# Arduino.net
KiCad netlist of a schematic drawn in Altium Designer
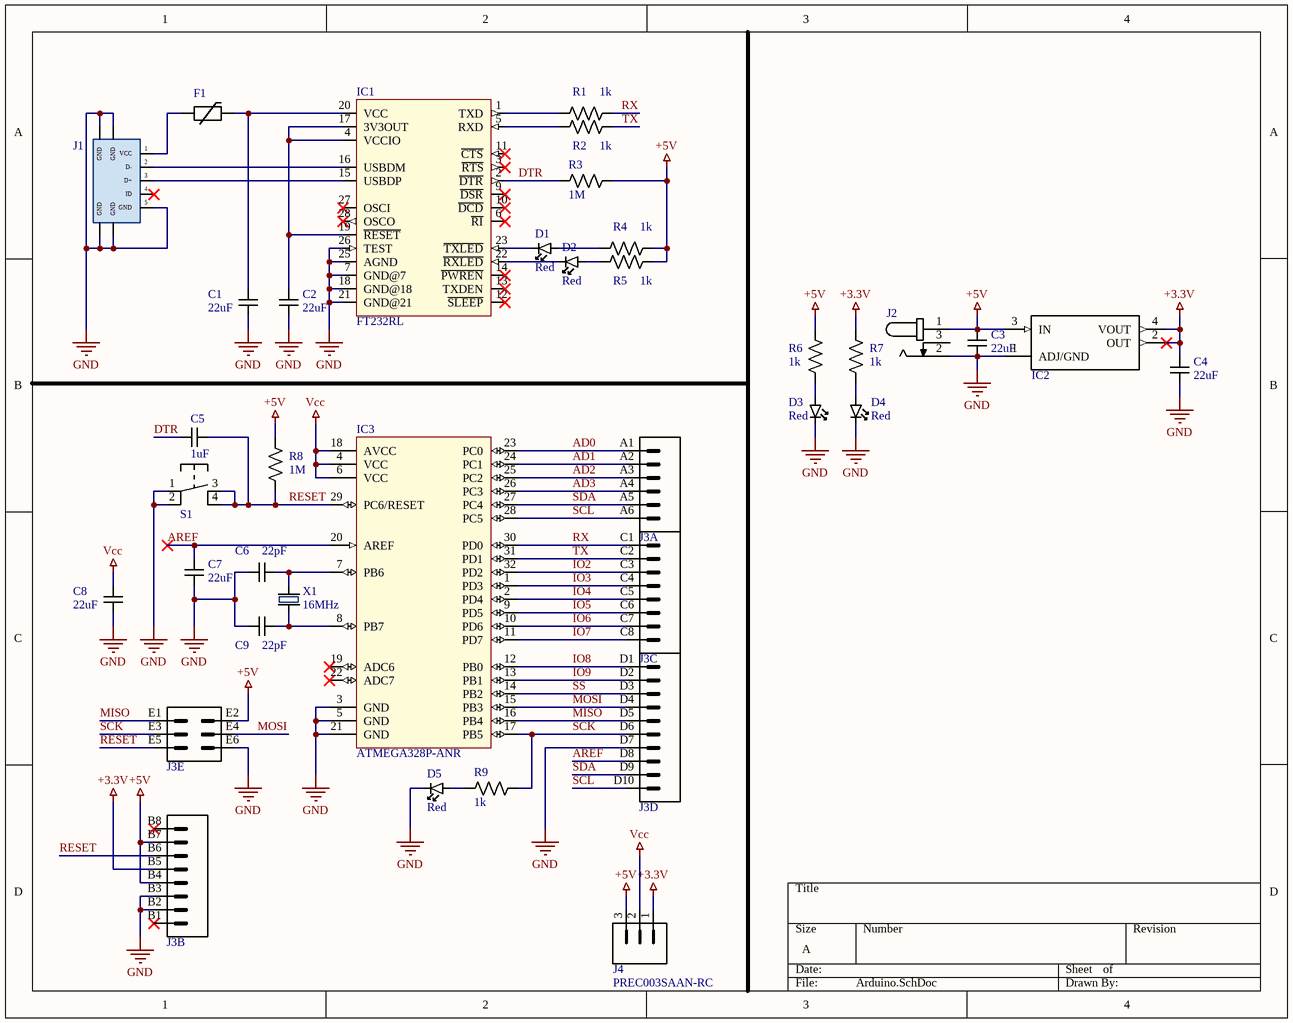
[diagram p0: Arduino.SchDoc]

(export (version "E")
  (design (tool "Eeschema 10.0.6"))
  (components
    (comp (ref "C1")
      (value "22uF")
      (footprint "CAP1206")
      (description "22µF ±20% 16V Ceramic Capacitor X5R 1206 (3216 Metric)")
      (fields (field (name "DIGIKEY PART") "1276-2728-1-ND"))
      (libsource (lib "Arduino") (part "1206_22uF"))
    )
    (comp (ref "C2")
      (value "22uF")
      (footprint "CAP1206")
      (description "22µF ±20% 16V Ceramic Capacitor X5R 1206 (3216 Metric)")
      (fields (field (name "DIGIKEY PART") "1276-2728-1-ND"))
      (libsource (lib "Arduino") (part "1206_22uF"))
    )
    (comp (ref "C3")
      (value "22uF")
      (footprint "CAP1206")
      (description "22µF ±20% 16V Ceramic Capacitor X5R 1206 (3216 Metric)")
      (fields (field (name "DIGIKEY PART") "1276-2728-1-ND"))
      (libsource (lib "Arduino") (part "1206_22uF"))
    )
    (comp (ref "C4")
      (value "22uF")
      (footprint "CAP1206")
      (description "22µF ±20% 16V Ceramic Capacitor X5R 1206 (3216 Metric)")
      (fields (field (name "DIGIKEY PART") "1276-2728-1-ND"))
      (libsource (lib "Arduino") (part "1206_22uF"))
    )
    (comp (ref "C5")
      (value "1uF")
      (footprint "CAP1206")
      (description "1µF ±20% 16V Ceramic Capacitor X7R 1206 (3216 Metric)")
      (fields (field (name "DIGIKEY PART") "399-8150-1-ND"))
      (libsource (lib "Arduino") (part "1206_1uF"))
    )
    (comp (ref "C6")
      (value "22pF")
      (footprint "CAP1206")
      (description "22pF ±5% 16V Ceramic Capacitor C0G, NP0 1206 (3216 Metric)")
      (fields (field (name "DIGIKEY PART") "732-7867-1-ND"))
      (libsource (lib "Arduino") (part "1206_22pF"))
    )
    (comp (ref "C7")
      (value "22uF")
      (footprint "CAP1206")
      (description "22µF ±20% 16V Ceramic Capacitor X5R 1206 (3216 Metric)")
      (fields (field (name "DIGIKEY PART") "1276-2728-1-ND"))
      (libsource (lib "Arduino") (part "1206_22uF"))
    )
    (comp (ref "C8")
      (value "22uF")
      (footprint "CAP1206")
      (description "22µF ±20% 16V Ceramic Capacitor X5R 1206 (3216 Metric)")
      (fields (field (name "DIGIKEY PART") "1276-2728-1-ND"))
      (libsource (lib "Arduino") (part "1206_22uF"))
    )
    (comp (ref "C9")
      (value "22pF")
      (footprint "CAP1206")
      (description "22pF ±5% 16V Ceramic Capacitor C0G, NP0 1206 (3216 Metric)")
      (fields (field (name "DIGIKEY PART") "732-7867-1-ND"))
      (libsource (lib "Arduino") (part "1206_22pF"))
    )
    (comp (ref "D1")
      (value "Red")
      (footprint "LED")
      (description "Red 638nm LED Indication - Discrete 1.8V 1206 (3216 Metric)")
      (fields (field (name "DIGIKEY PART") "160-1167-1-ND"))
      (libsource (lib "Arduino") (part "1206_RED_LED"))
    )
    (comp (ref "D2")
      (value "Red")
      (footprint "LED")
      (description "Red 638nm LED Indication - Discrete 1.8V 1206 (3216 Metric)")
      (fields (field (name "DIGIKEY PART") "160-1167-1-ND"))
      (libsource (lib "Arduino") (part "1206_RED_LED"))
    )
    (comp (ref "D3")
      (value "Red")
      (footprint "LED")
      (description "Red 638nm LED Indication - Discrete 1.8V 1206 (3216 Metric)")
      (fields (field (name "DIGIKEY PART") "160-1167-1-ND"))
      (libsource (lib "Arduino") (part "1206_RED_LED"))
    )
    (comp (ref "D4")
      (value "Red")
      (footprint "LED")
      (description "Red 638nm LED Indication - Discrete 1.8V 1206 (3216 Metric)")
      (fields (field (name "DIGIKEY PART") "160-1167-1-ND"))
      (libsource (lib "Arduino") (part "1206_RED_LED"))
    )
    (comp (ref "D5")
      (value "Red")
      (footprint "LED")
      (description "Red 638nm LED Indication - Discrete 1.8V 1206 (3216 Metric)")
      (fields (field (name "DIGIKEY PART") "160-1167-1-ND"))
      (libsource (lib "Arduino") (part "1206_RED_LED"))
    )
    (comp (ref "F1")
      (value "MF-MSMF050-2")
      (footprint "FUSE")
      (description "Polymeric PTC Resettable Fuse 15V 500mA Ih Surface Mount 1812 (4532 Metric), Concave")
      (fields (field (name "DIGIKEY PART") "MF-MSMF050-2CT-ND"))
      (libsource (lib "Arduino") (part "Fuse"))
    )
    (comp (ref "IC1")
      (value "FT232RL")
      (footprint "SSOP-28")
      (description "USB Bridge, USB to UART USB 2.0 UART Interface 28-SSOP")
      (fields (field (name "DIGIKEY PART") "768-1007-1-ND"))
      (libsource (lib "Arduino") (part "FTDI"))
    )
    (comp (ref "IC2")
      (value "AZ1117CH-3.3TRG1")
      (footprint "SOT223")
      (description "Linear Voltage Regulator IC Positive Fixed 1 Output 1A SOT-223")
      (fields (field (name "DIGIKEY PART") "AZ1117CH-3.3TRG1DICT-ND"))
      (libsource (lib "Arduino") (part "3.3V_LDO"))
    )
    (comp (ref "IC3")
      (value "ATMEGA328P-ANR")
      (footprint "TQFP")
      (description "AVR AVR® ATmega Microcontroller IC 8-Bit 20MHz 32KB (16K x 16) FLASH 32-TQFP (7x7)")
      (fields (field (name "DIGIKEY PART") "ATMEGA328P-ANRCT-ND"))
      (libsource (lib "Arduino") (part "ATMega328P"))
    )
    (comp (ref "J1")
      (value "XM7D-0512")
      (footprint "XM7D-0512")
      (description "USB - mini B USB 2.0 Receptacle Connector 5 Position Through Hole, Right Angle")
      (fields (field (name "DIGIKEY PART") "OR1205-ND"))
      (libsource (lib "Arduino") (part "USB"))
    )
    (comp (ref "J2")
      (value "Power Jack")
      (footprint "Power_Jack")
      (description "Power Barrel Connector Jack 2.10mm ID (0.083\"), 5.50mm OD (0.217\") Through Hole, Right Angle")
      (fields (field (name "DIGIKEY PART") "CP-102A-ND"))
      (libsource (lib "Arduino") (part "Power Jack"))
    )
    (comp (ref "J3")
      (value "Arduino_Shield")
      (footprint "ARDUINO_SHIELD")
      (libsource (lib "") (part "Arduino_Shield_1"))
    )
    (comp (ref "J4")
      (value "PREC003SAAN-RC")
      (footprint "3_PIN")
      (description "Connector Header Through Hole 3 position 0.100\" (2.54mm)")
      (fields (field (name "DIGIKEY PART") "S1012EC-03-ND"))
      (libsource (lib "Arduino") (part "3_PIN"))
    )
    (comp (ref "R1")
      (value "1k")
      (footprint "RES1206")
      (description "1 kOhms ±1% 0.5W, 1/2W Chip Resistor 1206 (3216 Metric) Anti-Sulfur, Moisture Resistant Thin Film")
      (fields (field (name "DIGIKEY PART") "RNCP1206FTD1K00CT-ND"))
      (libsource (lib "Arduino") (part "1206_1K"))
    )
    (comp (ref "R2")
      (value "1k")
      (footprint "RES1206")
      (description "1 kOhms ±1% 0.5W, 1/2W Chip Resistor 1206 (3216 Metric) Anti-Sulfur, Moisture Resistant Thin Film")
      (fields (field (name "DIGIKEY PART") "RNCP1206FTD1K00CT-ND"))
      (libsource (lib "Arduino") (part "1206_1K"))
    )
    (comp (ref "R3")
      (value "1M")
      (footprint "RES1206")
      (description "1 MOhms ±5% 0.25W, 1/4W Chip Resistor 1206 (3216 Metric) Automotive AEC-Q200 Thick Film")
      (fields (field (name "DIGIKEY PART") "Number RMCF1206JT1M00CT-ND"))
      (libsource (lib "Arduino") (part "1206_1M"))
    )
    (comp (ref "R4")
      (value "1k")
      (footprint "RES1206")
      (description "1 kOhms ±1% 0.5W, 1/2W Chip Resistor 1206 (3216 Metric) Anti-Sulfur, Moisture Resistant Thin Film")
      (fields (field (name "DIGIKEY PART") "RNCP1206FTD1K00CT-ND"))
      (libsource (lib "Arduino") (part "1206_1K"))
    )
    (comp (ref "R5")
      (value "1k")
      (footprint "RES1206")
      (description "1 kOhms ±1% 0.5W, 1/2W Chip Resistor 1206 (3216 Metric) Anti-Sulfur, Moisture Resistant Thin Film")
      (fields (field (name "DIGIKEY PART") "RNCP1206FTD1K00CT-ND"))
      (libsource (lib "Arduino") (part "1206_1K"))
    )
    (comp (ref "R6")
      (value "1k")
      (footprint "RES1206")
      (description "1 kOhms ±1% 0.5W, 1/2W Chip Resistor 1206 (3216 Metric) Anti-Sulfur, Moisture Resistant Thin Film")
      (fields (field (name "DIGIKEY PART") "RNCP1206FTD1K00CT-ND"))
      (libsource (lib "Arduino") (part "1206_1K"))
    )
    (comp (ref "R7")
      (value "1k")
      (footprint "RES1206")
      (description "1 kOhms ±1% 0.5W, 1/2W Chip Resistor 1206 (3216 Metric) Anti-Sulfur, Moisture Resistant Thin Film")
      (fields (field (name "DIGIKEY PART") "RNCP1206FTD1K00CT-ND"))
      (libsource (lib "Arduino") (part "1206_1K"))
    )
    (comp (ref "R8")
      (value "1M")
      (footprint "RES1206")
      (description "1 MOhms ±5% 0.25W, 1/4W Chip Resistor 1206 (3216 Metric) Automotive AEC-Q200 Thick Film")
      (fields (field (name "DIGIKEY PART") "Number RMCF1206JT1M00CT-ND"))
      (libsource (lib "Arduino") (part "1206_1M"))
    )
    (comp (ref "R9")
      (value "1k")
      (footprint "RES1206")
      (description "1 kOhms ±1% 0.5W, 1/2W Chip Resistor 1206 (3216 Metric) Anti-Sulfur, Moisture Resistant Thin Film")
      (fields (field (name "DIGIKEY PART") "RNCP1206FTD1K00CT-ND"))
      (libsource (lib "Arduino") (part "1206_1K"))
    )
    (comp (ref "S1")
      (value "TL3305AF160QG")
      (footprint "Switch")
      (description "Tactile Switch SPST-NO Top Actuated Surface Mount")
      (fields (field (name "DIGIKEY PART") "EG5350CT-ND"))
      (libsource (lib "Arduino") (part "Push_Button"))
    )
    (comp (ref "X1")
      (value "16MHz")
      (footprint "Crystal")
      (description "16MHz ±30ppm Crystal 18pF 40 Ohms HC-49/US")
      (fields (field (name "DIGIKEY PART") "535-10226-1-ND"))
      (libsource (lib "Arduino") (part "16MHz_Crystal"))
    )
  )
  (nets
    (net (code "1") (name "+3.3V") (class "Default")
      (node (ref "C4") (pin "2") (pinfunction "2_2") (pintype "passive"))
      (node (ref "IC2") (pin "2") (pinfunction "OUT_2") (pintype "output"))
      (node (ref "IC2") (pin "4") (pinfunction "VOUT_4") (pintype "output"))
      (node (ref "J3") (pin "B5") (pinfunction "5_B5") (pintype "passive"))
      (node (ref "J4") (pin "1") (pinfunction "1_1") (pintype "passive"))
      (node (ref "R7") (pin "2") (pintype "passive"))
    )
    (net (code "2") (name "+5V") (class "Default")
      (node (ref "C3") (pin "1") (pinfunction "1_1") (pintype "passive"))
      (node (ref "IC2") (pin "3") (pinfunction "IN_3") (pintype "input"))
      (node (ref "J2") (pin "1") (pinfunction "1_1") (pintype "passive"))
      (node (ref "J3") (pin "B4") (pinfunction "4_B4") (pintype "passive"))
      (node (ref "J3") (pin "B7") (pinfunction "7_B7") (pintype "passive"))
      (node (ref "J3") (pin "E2") (pinfunction "4_E2") (pintype "passive"))
      (node (ref "J4") (pin "3") (pinfunction "3_3") (pintype "passive"))
      (node (ref "R3") (pin "1") (pintype "passive"))
      (node (ref "R4") (pin "2") (pintype "passive"))
      (node (ref "R5") (pin "2") (pintype "passive"))
      (node (ref "R6") (pin "2") (pintype "passive"))
      (node (ref "R8") (pin "2") (pintype "passive"))
    )
    (net (code "3") (name "/AD0") (class "Default")
      (node (ref "IC3") (pin "23") (pinfunction "PC0_23") (pintype "bidirectional"))
      (node (ref "J3") (pin "A1") (pinfunction "1_A1") (pintype "passive"))
    )
    (net (code "4") (name "/AD1") (class "Default")
      (node (ref "IC3") (pin "24") (pinfunction "PC1_24") (pintype "bidirectional"))
      (node (ref "J3") (pin "A2") (pinfunction "2_A2") (pintype "passive"))
    )
    (net (code "5") (name "/AD2") (class "Default")
      (node (ref "IC3") (pin "25") (pinfunction "PC2_25") (pintype "bidirectional"))
      (node (ref "J3") (pin "A3") (pinfunction "3_A3") (pintype "passive"))
    )
    (net (code "6") (name "/AD3") (class "Default")
      (node (ref "IC3") (pin "26") (pinfunction "PC3_26") (pintype "bidirectional"))
      (node (ref "J3") (pin "A4") (pinfunction "4_A4") (pintype "passive"))
    )
    (net (code "7") (name "/AREF") (class "Default")
      (node (ref "C7") (pin "2") (pinfunction "2_2") (pintype "passive"))
      (node (ref "IC3") (pin "20") (pinfunction "AREF_20") (pintype "input"))
      (node (ref "J3") (pin "D8") (pinfunction "8_D8") (pintype "passive"))
    )
    (net (code "8") (name "/DTR") (class "Default")
      (node (ref "C5") (pin "1") (pinfunction "1_1") (pintype "passive"))
      (node (ref "IC1") (pin "2") (pinfunction "~{DTR}_2") (pintype "output"))
      (node (ref "R3") (pin "2") (pintype "passive"))
    )
    (net (code "9") (name "/IO2") (class "Default")
      (node (ref "IC3") (pin "32") (pinfunction "PD2_32") (pintype "bidirectional"))
      (node (ref "J3") (pin "C3") (pinfunction "3_C3") (pintype "passive"))
    )
    (net (code "10") (name "/IO3") (class "Default")
      (node (ref "IC3") (pin "1") (pinfunction "PD3_1") (pintype "bidirectional"))
      (node (ref "J3") (pin "C4") (pinfunction "4_C4") (pintype "passive"))
    )
    (net (code "11") (name "/IO4") (class "Default")
      (node (ref "IC3") (pin "2") (pinfunction "PD4_2") (pintype "bidirectional"))
      (node (ref "J3") (pin "C5") (pinfunction "5_C5") (pintype "passive"))
    )
    (net (code "12") (name "/IO5") (class "Default")
      (node (ref "IC3") (pin "9") (pinfunction "PD5_9") (pintype "bidirectional"))
      (node (ref "J3") (pin "C6") (pinfunction "6_C6") (pintype "passive"))
    )
    (net (code "13") (name "/IO6") (class "Default")
      (node (ref "IC3") (pin "10") (pinfunction "PD6_10") (pintype "bidirectional"))
      (node (ref "J3") (pin "C7") (pinfunction "7_C7") (pintype "passive"))
    )
    (net (code "14") (name "/IO7") (class "Default")
      (node (ref "IC3") (pin "11") (pinfunction "PD7_11") (pintype "bidirectional"))
      (node (ref "J3") (pin "C8") (pinfunction "8_C8") (pintype "passive"))
    )
    (net (code "15") (name "/IO8") (class "Default")
      (node (ref "IC3") (pin "12") (pinfunction "PB0_12") (pintype "bidirectional"))
      (node (ref "J3") (pin "D1") (pinfunction "1_D1") (pintype "passive"))
    )
    (net (code "16") (name "/IO9") (class "Default")
      (node (ref "IC3") (pin "13") (pinfunction "PB1_13") (pintype "bidirectional"))
      (node (ref "J3") (pin "D2") (pinfunction "2_D2") (pintype "passive"))
    )
    (net (code "17") (name "/MISO") (class "Default")
      (node (ref "IC3") (pin "16") (pinfunction "PB4_16") (pintype "bidirectional"))
      (node (ref "J3") (pin "D5") (pinfunction "5_D5") (pintype "passive"))
      (node (ref "J3") (pin "E1") (pinfunction "1_E1") (pintype "passive"))
    )
    (net (code "18") (name "/MOSI") (class "Default")
      (node (ref "IC3") (pin "15") (pinfunction "PB3_15") (pintype "bidirectional"))
      (node (ref "J3") (pin "D4") (pinfunction "4_D4") (pintype "passive"))
      (node (ref "J3") (pin "E4") (pinfunction "5_E4") (pintype "passive"))
    )
    (net (code "19") (name "/RESET") (class "Default")
      (node (ref "C5") (pin "2") (pinfunction "2_2") (pintype "passive"))
      (node (ref "IC3") (pin "29") (pinfunction "PC6/RESET_29") (pintype "bidirectional"))
      (node (ref "J3") (pin "B6") (pinfunction "6_B6") (pintype "passive"))
      (node (ref "J3") (pin "E5") (pinfunction "3_E5") (pintype "passive"))
      (node (ref "R8") (pin "1") (pintype "passive"))
      (node (ref "S1") (pin "3") (pinfunction "3_3") (pintype "passive"))
      (node (ref "S1") (pin "4") (pinfunction "4_4") (pintype "passive"))
    )
    (net (code "20") (name "/RX") (class "Default")
      (node (ref "IC3") (pin "30") (pinfunction "PD0_30") (pintype "bidirectional"))
      (node (ref "J3") (pin "C1") (pinfunction "1_C1") (pintype "passive"))
      (node (ref "R1") (pin "2") (pintype "passive"))
    )
    (net (code "21") (name "/SCK") (class "Default")
      (node (ref "IC3") (pin "17") (pinfunction "PB5_17") (pintype "bidirectional"))
      (node (ref "J3") (pin "D6") (pinfunction "6_D6") (pintype "passive"))
      (node (ref "J3") (pin "E3") (pinfunction "2_E3") (pintype "passive"))
      (node (ref "R9") (pin "2") (pintype "passive"))
    )
    (net (code "22") (name "/SCL") (class "Default")
      (node (ref "IC3") (pin "28") (pinfunction "PC5_28") (pintype "bidirectional"))
      (node (ref "J3") (pin "A6") (pinfunction "6_A6") (pintype "passive"))
      (node (ref "J3") (pin "D10") (pinfunction "10_D10") (pintype "passive"))
    )
    (net (code "23") (name "/SDA") (class "Default")
      (node (ref "IC3") (pin "27") (pinfunction "PC4_27") (pintype "bidirectional"))
      (node (ref "J3") (pin "A5") (pinfunction "5_A5") (pintype "passive"))
      (node (ref "J3") (pin "D9") (pinfunction "9_D9") (pintype "passive"))
    )
    (net (code "24") (name "/SS") (class "Default")
      (node (ref "IC3") (pin "14") (pinfunction "PB2_14") (pintype "bidirectional"))
      (node (ref "J3") (pin "D3") (pinfunction "3_D3") (pintype "passive"))
    )
    (net (code "25") (name "/TX") (class "Default")
      (node (ref "IC3") (pin "31") (pinfunction "PD1_31") (pintype "bidirectional"))
      (node (ref "J3") (pin "C2") (pinfunction "2_C2") (pintype "passive"))
      (node (ref "R2") (pin "2") (pintype "passive"))
    )
    (net (code "26") (name "GND") (class "Default")
      (node (ref "C1") (pin "1") (pinfunction "1_1") (pintype "passive"))
      (node (ref "C2") (pin "1") (pinfunction "1_1") (pintype "passive"))
      (node (ref "C3") (pin "2") (pinfunction "2_2") (pintype "passive"))
      (node (ref "C4") (pin "1") (pinfunction "1_1") (pintype "passive"))
      (node (ref "C6") (pin "1") (pinfunction "1_1") (pintype "passive"))
      (node (ref "C7") (pin "1") (pinfunction "1_1") (pintype "passive"))
      (node (ref "C8") (pin "1") (pinfunction "1_1") (pintype "passive"))
      (node (ref "C9") (pin "1") (pinfunction "1_1") (pintype "passive"))
      (node (ref "D3") (pin "1") (pinfunction "1_1") (pintype "passive"))
      (node (ref "D4") (pin "1") (pinfunction "1_1") (pintype "passive"))
      (node (ref "D5") (pin "1") (pinfunction "1_1") (pintype "passive"))
      (node (ref "IC1") (pin "18") (pinfunction "GND@18_18") (pintype "power_in"))
      (node (ref "IC1") (pin "21") (pinfunction "GND@21_21") (pintype "power_in"))
      (node (ref "IC1") (pin "25") (pinfunction "AGND_25") (pintype "power_in"))
      (node (ref "IC1") (pin "26") (pinfunction "TEST_26") (pintype "input"))
      (node (ref "IC1") (pin "7") (pinfunction "GND@7_7") (pintype "power_in"))
      (node (ref "IC2") (pin "1") (pinfunction "ADJ/GND_1") (pintype "passive"))
      (node (ref "IC3") (pin "21") (pinfunction "GND_21") (pintype "power_in"))
      (node (ref "IC3") (pin "3") (pinfunction "GND_3") (pintype "power_in"))
      (node (ref "IC3") (pin "5") (pinfunction "GND_5") (pintype "power_in"))
      (node (ref "J1") (pin "5") (pinfunction "GND_5") (pintype "passive"))
      (node (ref "J1") (pin "SH1") (pinfunction "GND_SH1") (pintype "passive"))
      (node (ref "J1") (pin "SH2") (pinfunction "GND_SH2") (pintype "passive"))
      (node (ref "J1") (pin "SH3") (pinfunction "GND_SH3") (pintype "passive"))
      (node (ref "J1") (pin "SH4") (pinfunction "GND_SH4") (pintype "passive"))
      (node (ref "J2") (pin "2") (pinfunction "2_2") (pintype "passive"))
      (node (ref "J3") (pin "B2") (pinfunction "2_B2") (pintype "passive"))
      (node (ref "J3") (pin "B3") (pinfunction "3_B3") (pintype "passive"))
      (node (ref "J3") (pin "D7") (pinfunction "7_D7") (pintype "passive"))
      (node (ref "J3") (pin "E6") (pinfunction "6_E6") (pintype "passive"))
      (node (ref "S1") (pin "1") (pinfunction "1_1") (pintype "passive"))
      (node (ref "S1") (pin "2") (pinfunction "2_2") (pintype "passive"))
    )
    (net (code "27") (name "Net-(D1-Pad2)") (class "Default")
      (node (ref "D1") (pin "2") (pinfunction "2_2") (pintype "passive"))
      (node (ref "R4") (pin "1") (pintype "passive"))
    )
    (net (code "28") (name "Net-(D2-Pad2)") (class "Default")
      (node (ref "D2") (pin "2") (pinfunction "2_2") (pintype "passive"))
      (node (ref "R5") (pin "1") (pintype "passive"))
    )
    (net (code "29") (name "Net-(D3-Pad2)") (class "Default")
      (node (ref "D3") (pin "2") (pinfunction "2_2") (pintype "passive"))
      (node (ref "R6") (pin "1") (pintype "passive"))
    )
    (net (code "30") (name "Net-(D4-Pad2)") (class "Default")
      (node (ref "D4") (pin "2") (pinfunction "2_2") (pintype "passive"))
      (node (ref "R7") (pin "1") (pintype "passive"))
    )
    (net (code "31") (name "Net-(D5-Pad2)") (class "Default")
      (node (ref "D5") (pin "2") (pinfunction "2_2") (pintype "passive"))
      (node (ref "R9") (pin "1") (pintype "passive"))
    )
    (net (code "32") (name "Net-(IC1-3V3OUT)") (class "Default")
      (node (ref "C2") (pin "2") (pinfunction "2_2") (pintype "passive"))
      (node (ref "IC1") (pin "17") (pinfunction "3V3OUT_17") (pintype "power_in"))
      (node (ref "IC1") (pin "19") (pinfunction "~{RESET}_19") (pintype "passive"))
      (node (ref "IC1") (pin "4") (pinfunction "VCCIO_4") (pintype "power_in"))
    )
    (net (code "33") (name "Net-(IC1-RXD)") (class "Default")
      (node (ref "IC1") (pin "5") (pinfunction "RXD_5") (pintype "input"))
      (node (ref "R2") (pin "1") (pintype "passive"))
    )
    (net (code "34") (name "Net-(IC1-TXD)") (class "Default")
      (node (ref "IC1") (pin "1") (pinfunction "TXD_1") (pintype "output"))
      (node (ref "R1") (pin "1") (pintype "passive"))
    )
    (net (code "35") (name "Net-(IC1-USBDM)") (class "Default")
      (node (ref "IC1") (pin "16") (pinfunction "USBDM_16") (pintype "bidirectional"))
      (node (ref "J1") (pin "2") (pinfunction "D-_2") (pintype "passive"))
    )
    (net (code "36") (name "Net-(IC1-USBDP)") (class "Default")
      (node (ref "IC1") (pin "15") (pinfunction "USBDP_15") (pintype "bidirectional"))
      (node (ref "J1") (pin "3") (pinfunction "D+_3") (pintype "passive"))
    )
    (net (code "37") (name "Net-(IC1-VCC)") (class "Default")
      (node (ref "C1") (pin "2") (pinfunction "2_2") (pintype "passive"))
      (node (ref "F1") (pin "2") (pinfunction "2_2") (pintype "passive"))
      (node (ref "IC1") (pin "20") (pinfunction "VCC_20") (pintype "power_in"))
    )
    (net (code "38") (name "Net-(IC1-~{RXLED})") (class "Default")
      (node (ref "D2") (pin "1") (pinfunction "1_1") (pintype "passive"))
      (node (ref "IC1") (pin "22") (pinfunction "~{RXLED}_22") (pintype "input"))
    )
    (net (code "39") (name "Net-(IC1-~{TXLED})") (class "Default")
      (node (ref "D1") (pin "1") (pinfunction "1_1") (pintype "passive"))
      (node (ref "IC1") (pin "23") (pinfunction "~{TXLED}_23") (pintype "input"))
    )
    (net (code "40") (name "Net-(IC3-PB6)") (class "Default")
      (node (ref "C6") (pin "2") (pinfunction "2_2") (pintype "passive"))
      (node (ref "IC3") (pin "7") (pinfunction "PB6_7") (pintype "bidirectional"))
      (node (ref "X1") (pin "2") (pinfunction "2_2") (pintype "passive"))
    )
    (net (code "41") (name "Net-(IC3-PB7)") (class "Default")
      (node (ref "C9") (pin "2") (pinfunction "2_2") (pintype "passive"))
      (node (ref "IC3") (pin "8") (pinfunction "PB7_8") (pintype "bidirectional"))
      (node (ref "X1") (pin "1") (pinfunction "1_1") (pintype "passive"))
    )
    (net (code "42") (name "Net-(J1-VCC)") (class "Default")
      (node (ref "F1") (pin "1") (pinfunction "1_1") (pintype "passive"))
      (node (ref "J1") (pin "1") (pinfunction "VCC_1") (pintype "passive"))
    )
    (net (code "43") (name "Vcc") (class "Default")
      (node (ref "C8") (pin "2") (pinfunction "2_2") (pintype "passive"))
      (node (ref "IC3") (pin "18") (pinfunction "AVCC_18") (pintype "power_in"))
      (node (ref "IC3") (pin "4") (pinfunction "VCC_4") (pintype "power_in"))
      (node (ref "IC3") (pin "6") (pinfunction "VCC_6") (pintype "power_in"))
      (node (ref "J4") (pin "2") (pinfunction "2_2") (pintype "passive"))
    )
    (net (code "44") (name "unconnected-(IC1-OSCI-Pad27)") (class "Default")
      (node (ref "IC1") (pin "27") (pinfunction "OSCI_27") (pintype "passive+no_connect"))
    )
    (net (code "45") (name "unconnected-(IC1-OSCO-Pad28)") (class "Default")
      (node (ref "IC1") (pin "28") (pinfunction "OSCO_28") (pintype "output+no_connect"))
    )
    (net (code "46") (name "unconnected-(IC1-TXDEN-Pad13)") (class "Default")
      (node (ref "IC1") (pin "13") (pinfunction "TXDEN_13") (pintype "passive+no_connect"))
    )
    (net (code "47") (name "unconnected-(IC1-~{CTS}-Pad11)") (class "Default")
      (node (ref "IC1") (pin "11") (pinfunction "~{CTS}_11") (pintype "input+no_connect"))
    )
    (net (code "48") (name "unconnected-(IC1-~{DCD}-Pad10)") (class "Default")
      (node (ref "IC1") (pin "10") (pinfunction "~{DCD}_10") (pintype "passive+no_connect"))
    )
    (net (code "49") (name "unconnected-(IC1-~{DSR}-Pad9)") (class "Default")
      (node (ref "IC1") (pin "9") (pinfunction "~{DSR}_9") (pintype "passive+no_connect"))
    )
    (net (code "50") (name "unconnected-(IC1-~{PWREN}-Pad14)") (class "Default")
      (node (ref "IC1") (pin "14") (pinfunction "~{PWREN}_14") (pintype "passive+no_connect"))
    )
    (net (code "51") (name "unconnected-(IC1-~{RI}-Pad6)") (class "Default")
      (node (ref "IC1") (pin "6") (pinfunction "~{RI}_6") (pintype "passive+no_connect"))
    )
    (net (code "52") (name "unconnected-(IC1-~{RTS}-Pad3)") (class "Default")
      (node (ref "IC1") (pin "3") (pinfunction "~{RTS}_3") (pintype "output+no_connect"))
    )
    (net (code "53") (name "unconnected-(IC1-~{SLEEP}-Pad12)") (class "Default")
      (node (ref "IC1") (pin "12") (pinfunction "~{SLEEP}_12") (pintype "passive+no_connect"))
    )
    (net (code "54") (name "unconnected-(IC3-ADC6-Pad19)") (class "Default")
      (node (ref "IC3") (pin "19") (pinfunction "ADC6_19") (pintype "bidirectional+no_connect"))
    )
    (net (code "55") (name "unconnected-(IC3-ADC7-Pad22)") (class "Default")
      (node (ref "IC3") (pin "22") (pinfunction "ADC7_22") (pintype "bidirectional+no_connect"))
    )
    (net (code "56") (name "unconnected-(J1-ID-Pad4)") (class "Default")
      (node (ref "J1") (pin "4") (pinfunction "ID_4") (pintype "passive+no_connect"))
    )
    (net (code "57") (name "unconnected-(J2-Pad3)") (class "Default")
      (node (ref "J2") (pin "3") (pinfunction "3_3") (pintype "passive"))
    )
    (net (code "58") (name "unconnected-(J3B-1-PadB1)") (class "Default")
      (node (ref "J3") (pin "B1") (pinfunction "1_B1") (pintype "passive+no_connect"))
    )
    (net (code "59") (name "unconnected-(J3B-8-PadB8)") (class "Default")
      (node (ref "J3") (pin "B8") (pinfunction "8_B8") (pintype "passive+no_connect"))
    )
  )
)
